# PCB_Schematic.net
KiCad netlist of a schematic drawn in Altium Designer
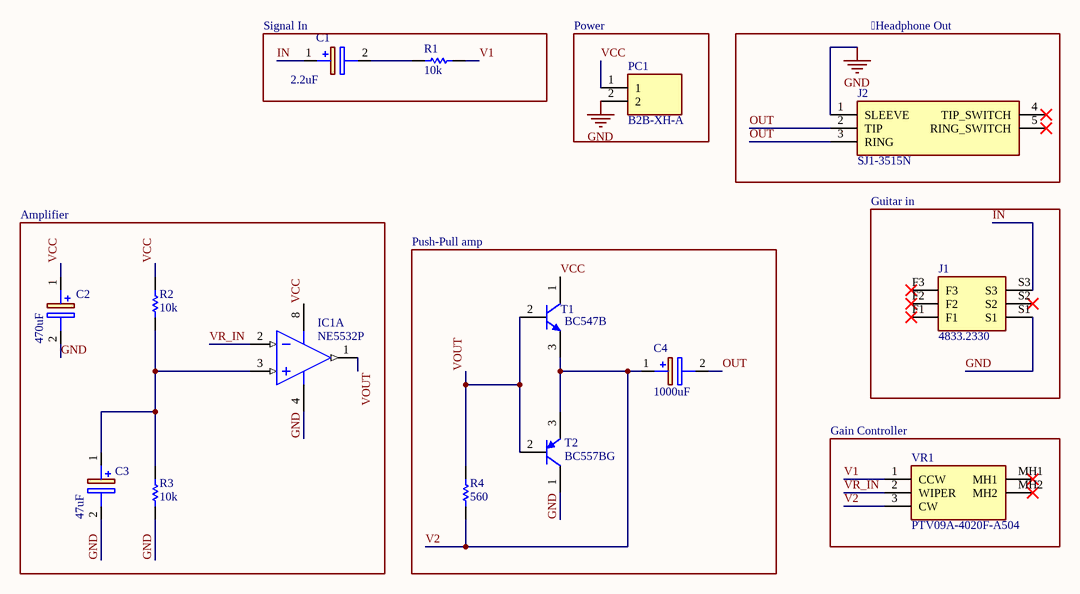
[diagram p0: PCB Schematic.SchDoc]

(export (version "E")
  (design (tool "Eeschema 10.0.6"))
  (components
    (comp (ref "C1")
      (value "2.2uF")
      (footprint "SamacSys:CAPPRD200W50D500H1250")
      (description "Capacitor Polarised")
      (fields
        (field (name "MANUFACTURER_PART_NUMBER") "ESK225M050AC3KA")
        (field (name "MOUSER PART NUMBER") "80-ESK225M050AC3KA")
      )
      (libsource (lib "*") (part "ESK225M050AC3KA"))
    )
    (comp (ref "C2")
      (value "470uF")
      (footprint "SamacSys:CAPPRD500W65D1000H1700")
      (description "Capacitor Polarised")
      (fields
        (field (name "MANUFACTURER_PART_NUMBER") "ECA-1VM471B")
        (field (name "MOUSER PART NUMBER") "667-ECA-1VM471B")
      )
      (libsource (lib "*") (part "ECA-1VM471B"))
    )
    (comp (ref "C3")
      (value "47uF")
      (footprint "SamacSys:CAPPRD500W60D1300H2200")
      (description "Capacitor Polarised")
      (fields
        (field (name "MANUFACTURER_PART_NUMBER") "UCS2E470MHD1TO")
        (field (name "MOUSER PART NUMBER") "647-UCS2E470MHD1TO")
      )
      (libsource (lib "*") (part "UCS2E470MHD1TO"))
    )
    (comp (ref "C4")
      (value "1000uF")
      (footprint "SamacSys:CAPPRD750W85D1600H2200")
      (description "Capacitor Polarised")
      (fields
        (field (name "MANUFACTURER_PART_NUMBER") "EEU-FC1V102S")
        (field (name "MOUSER PART NUMBER") "667-EEU-FC1V102S")
      )
      (libsource (lib "*") (part "EEU-FC1V102S"))
    )
    (comp (ref "IC1")
      (value "NE5532P")
      (footprint "P0008A")
      (fields (field (name "MANUFACTURER") "Texas Instruments"))
      (libsource (lib "Altium Content Vault") (part "TI-AMP-D6-2-8_D"))
    )
    (comp (ref "J1")
      (value "4833.2330")
      (footprint "SamacSys:48332330")
      (description "Connector")
      (fields (field (name "MOUSER PART NUMBER") "693-4833.233"))
      (libsource (lib "*") (part "4833.2330"))
    )
    (comp (ref "J2")
      (value "SJ1-3515N")
      (footprint "SamacSys:SJ13515N")
      (description "Connector")
      (fields (field (name "MOUSER PART NUMBER") "490-SJ1-3515N"))
      (libsource (lib "*") (part "SJ1-3515N"))
    )
    (comp (ref "PC1")
      (value "B2B-XH-A")
      (footprint "SamacSys:SHDR2W64P0X250_1X2_740X575X700P")
      (description "Connector")
      (libsource (lib "*") (part "B2B-XH-A"))
    )
    (comp (ref "R1")
      (value "10k")
      (footprint "RESA60-630X240")
      (description "Axial Resistor, 10 KOhm, +/- 1%, 0.25 W, -55 to 155 degC, 2-Pin THD, RoHS, Bulk")
      (fields (field (name "TOLERANCE") "1%") (field (name "MANUFACTURER") "Yageo"))
      (libsource (lib "Altium Content Vault") (part "RES-2"))
    )
    (comp (ref "R2")
      (value "10k")
      (footprint "RESA60-630X240")
      (description "Axial Resistor, 10 KOhm, +/- 1%, 0.25 W, -55 to 155 degC, 2-Pin THD, RoHS, Bulk")
      (fields (field (name "TOLERANCE") "1%") (field (name "MANUFACTURER") "Yageo"))
      (libsource (lib "Altium Content Vault") (part "RES-2"))
    )
    (comp (ref "R3")
      (value "10k")
      (footprint "RESA60-630X240")
      (description "Axial Resistor, 10 KOhm, +/- 1%, 0.25 W, -55 to 155 degC, 2-Pin THD, RoHS, Bulk")
      (fields (field (name "TOLERANCE") "1%") (field (name "MANUFACTURER") "Yageo"))
      (libsource (lib "Altium Content Vault") (part "RES-2"))
    )
    (comp (ref "R4")
      (value "560")
      (footprint "RESA60-630X240")
      (description "Axial Resistor, 10 KOhm, +/- 1%, 0.25 W, -55 to 155 degC, 2-Pin THD, RoHS, Bulk")
      (fields (field (name "TOLERANCE") "1%") (field (name "MANUFACTURER") "Yageo"))
      (libsource (lib "Altium Content Vault") (part "RES-2"))
    )
    (comp (ref "T1")
      (value "BC547B")
      (footprint "ONSC-TO-92-3-29-11")
      (description "Amplifier Transistor, NPN Silicon, 3-Pin TO-92, Bulk Box")
      (fields (field (name "MANUFACTURER") "On Semiconductor"))
      (libsource (lib "Altium Content Vault") (part "ONSC-NPN-C1B2E3-3"))
    )
    (comp (ref "T2")
      (value "BC557BG")
      (footprint "ONSC-TO-92-3-29-11")
      (description "Amplifier Transistor, PNP Silicon, 3-Pin TO-92, Pb-Free, Bulk Box")
      (fields (field (name "MANUFACTURER") "On Semiconductor"))
      (libsource (lib "Altium Content Vault") (part "ONSC-PNP-C1B2E3-3"))
    )
    (comp (ref "VR1")
      (value "PTV09A-4020F-A504")
      (footprint "SamacSys:PTV09A4020FA504")
      (description "Variable Resistor")
      (fields (field (name "MOUSER PART NUMBER") "652-PTV09A-4020FA504"))
      (libsource (lib "*") (part "PTV09A-4020F-A504"))
    )
  )
  (nets
    (net (code "1") (name "/IN") (class "Default")
      (node (ref "C1") (pin "1") (pinfunction "+_1") (pintype "passive"))
      (node (ref "J1") (pin "S3") (pinfunction "S3_S3") (pintype "passive"))
    )
    (net (code "2") (name "/OUT") (class "Default")
      (node (ref "C4") (pin "2") (pinfunction "-_2") (pintype "passive"))
      (node (ref "J2") (pin "2") (pinfunction "TIP_2") (pintype "passive"))
      (node (ref "J2") (pin "3") (pinfunction "RING_3") (pintype "passive"))
    )
    (net (code "3") (name "/V1") (class "Default")
      (node (ref "R1") (pin "2") (pinfunction "2_2") (pintype "passive"))
      (node (ref "VR1") (pin "1") (pinfunction "CCW_1") (pintype "passive"))
    )
    (net (code "4") (name "/V2") (class "Default")
      (node (ref "C4") (pin "1") (pinfunction "+_1") (pintype "passive"))
      (node (ref "R4") (pin "1") (pinfunction "1_1") (pintype "passive"))
      (node (ref "T1") (pin "3") (pinfunction "E_3") (pintype "passive"))
      (node (ref "T2") (pin "3") (pinfunction "E_3") (pintype "passive"))
      (node (ref "VR1") (pin "3") (pinfunction "CW_3") (pintype "passive"))
    )
    (net (code "5") (name "/VCC") (class "Default")
      (node (ref "C2") (pin "1") (pinfunction "+_1") (pintype "passive"))
      (node (ref "IC1") (pin "8") (pinfunction "VCC+_8") (pintype "power_in"))
      (node (ref "PC1") (pin "1") (pinfunction "1_1") (pintype "passive"))
      (node (ref "R2") (pin "2") (pinfunction "2_2") (pintype "passive"))
      (node (ref "T1") (pin "1") (pinfunction "C_1") (pintype "passive"))
    )
    (net (code "6") (name "/VOUT") (class "Default")
      (node (ref "IC1") (pin "1") (pinfunction "OUT1_1") (pintype "output"))
      (node (ref "R4") (pin "2") (pinfunction "2_2") (pintype "passive"))
      (node (ref "T1") (pin "2") (pinfunction "B_2") (pintype "passive"))
      (node (ref "T2") (pin "2") (pinfunction "B_2") (pintype "passive"))
    )
    (net (code "7") (name "/VR_IN") (class "Default")
      (node (ref "IC1") (pin "2") (pinfunction "IN1-_2") (pintype "input"))
      (node (ref "VR1") (pin "2") (pinfunction "WIPER_2") (pintype "passive"))
    )
    (net (code "8") (name "GND") (class "Default")
      (node (ref "C2") (pin "2") (pinfunction "-_2") (pintype "passive"))
      (node (ref "C3") (pin "2") (pinfunction "-_2") (pintype "passive"))
      (node (ref "IC1") (pin "4") (pinfunction "VCC-_4") (pintype "power_in"))
      (node (ref "J1") (pin "S1") (pinfunction "S1_S1") (pintype "passive"))
      (node (ref "J2") (pin "1") (pinfunction "SLEEVE_1") (pintype "passive"))
      (node (ref "PC1") (pin "2") (pinfunction "2_2") (pintype "passive"))
      (node (ref "R3") (pin "1") (pinfunction "1_1") (pintype "passive"))
      (node (ref "T2") (pin "1") (pinfunction "C_1") (pintype "passive"))
    )
    (net (code "9") (name "Net-(C1--)") (class "Default")
      (node (ref "C1") (pin "2") (pinfunction "-_2") (pintype "passive"))
      (node (ref "R1") (pin "1") (pinfunction "1_1") (pintype "passive"))
    )
    (net (code "10") (name "Net-(C3-+)") (class "Default")
      (node (ref "C3") (pin "1") (pinfunction "+_1") (pintype "passive"))
      (node (ref "IC1") (pin "3") (pinfunction "IN1+_3") (pintype "input"))
      (node (ref "R2") (pin "1") (pinfunction "1_1") (pintype "passive"))
      (node (ref "R3") (pin "2") (pinfunction "2_2") (pintype "passive"))
    )
    (net (code "11") (name "unconnected-(J1-PadF1)") (class "Default")
      (node (ref "J1") (pin "F1") (pinfunction "F1_F1") (pintype "passive+no_connect"))
    )
    (net (code "12") (name "unconnected-(J1-PadF2)") (class "Default")
      (node (ref "J1") (pin "F2") (pinfunction "F2_F2") (pintype "passive+no_connect"))
    )
    (net (code "13") (name "unconnected-(J1-PadF3)") (class "Default")
      (node (ref "J1") (pin "F3") (pinfunction "F3_F3") (pintype "passive+no_connect"))
    )
    (net (code "14") (name "unconnected-(J1-PadS2)") (class "Default")
      (node (ref "J1") (pin "S2") (pinfunction "S2_S2") (pintype "passive+no_connect"))
    )
    (net (code "15") (name "unconnected-(J2-RING_SWITCH-Pad5)") (class "Default")
      (node (ref "J2") (pin "5") (pinfunction "RING_SWITCH_5") (pintype "passive+no_connect"))
    )
    (net (code "16") (name "unconnected-(J2-TIP_SWITCH-Pad4)") (class "Default")
      (node (ref "J2") (pin "4") (pinfunction "TIP_SWITCH_4") (pintype "passive+no_connect"))
    )
    (net (code "17") (name "unconnected-(VR1-PadMH1)") (class "Default")
      (node (ref "VR1") (pin "MH1") (pinfunction "MH1_MH1") (pintype "passive+no_connect"))
    )
    (net (code "18") (name "unconnected-(VR1-PadMH2)") (class "Default")
      (node (ref "VR1") (pin "MH2") (pinfunction "MH2_MH2") (pintype "passive+no_connect"))
    )
  )
)
